# GPS_Tracker_Base_Station.net
KiCad netlist of a schematic drawn in EAGLE
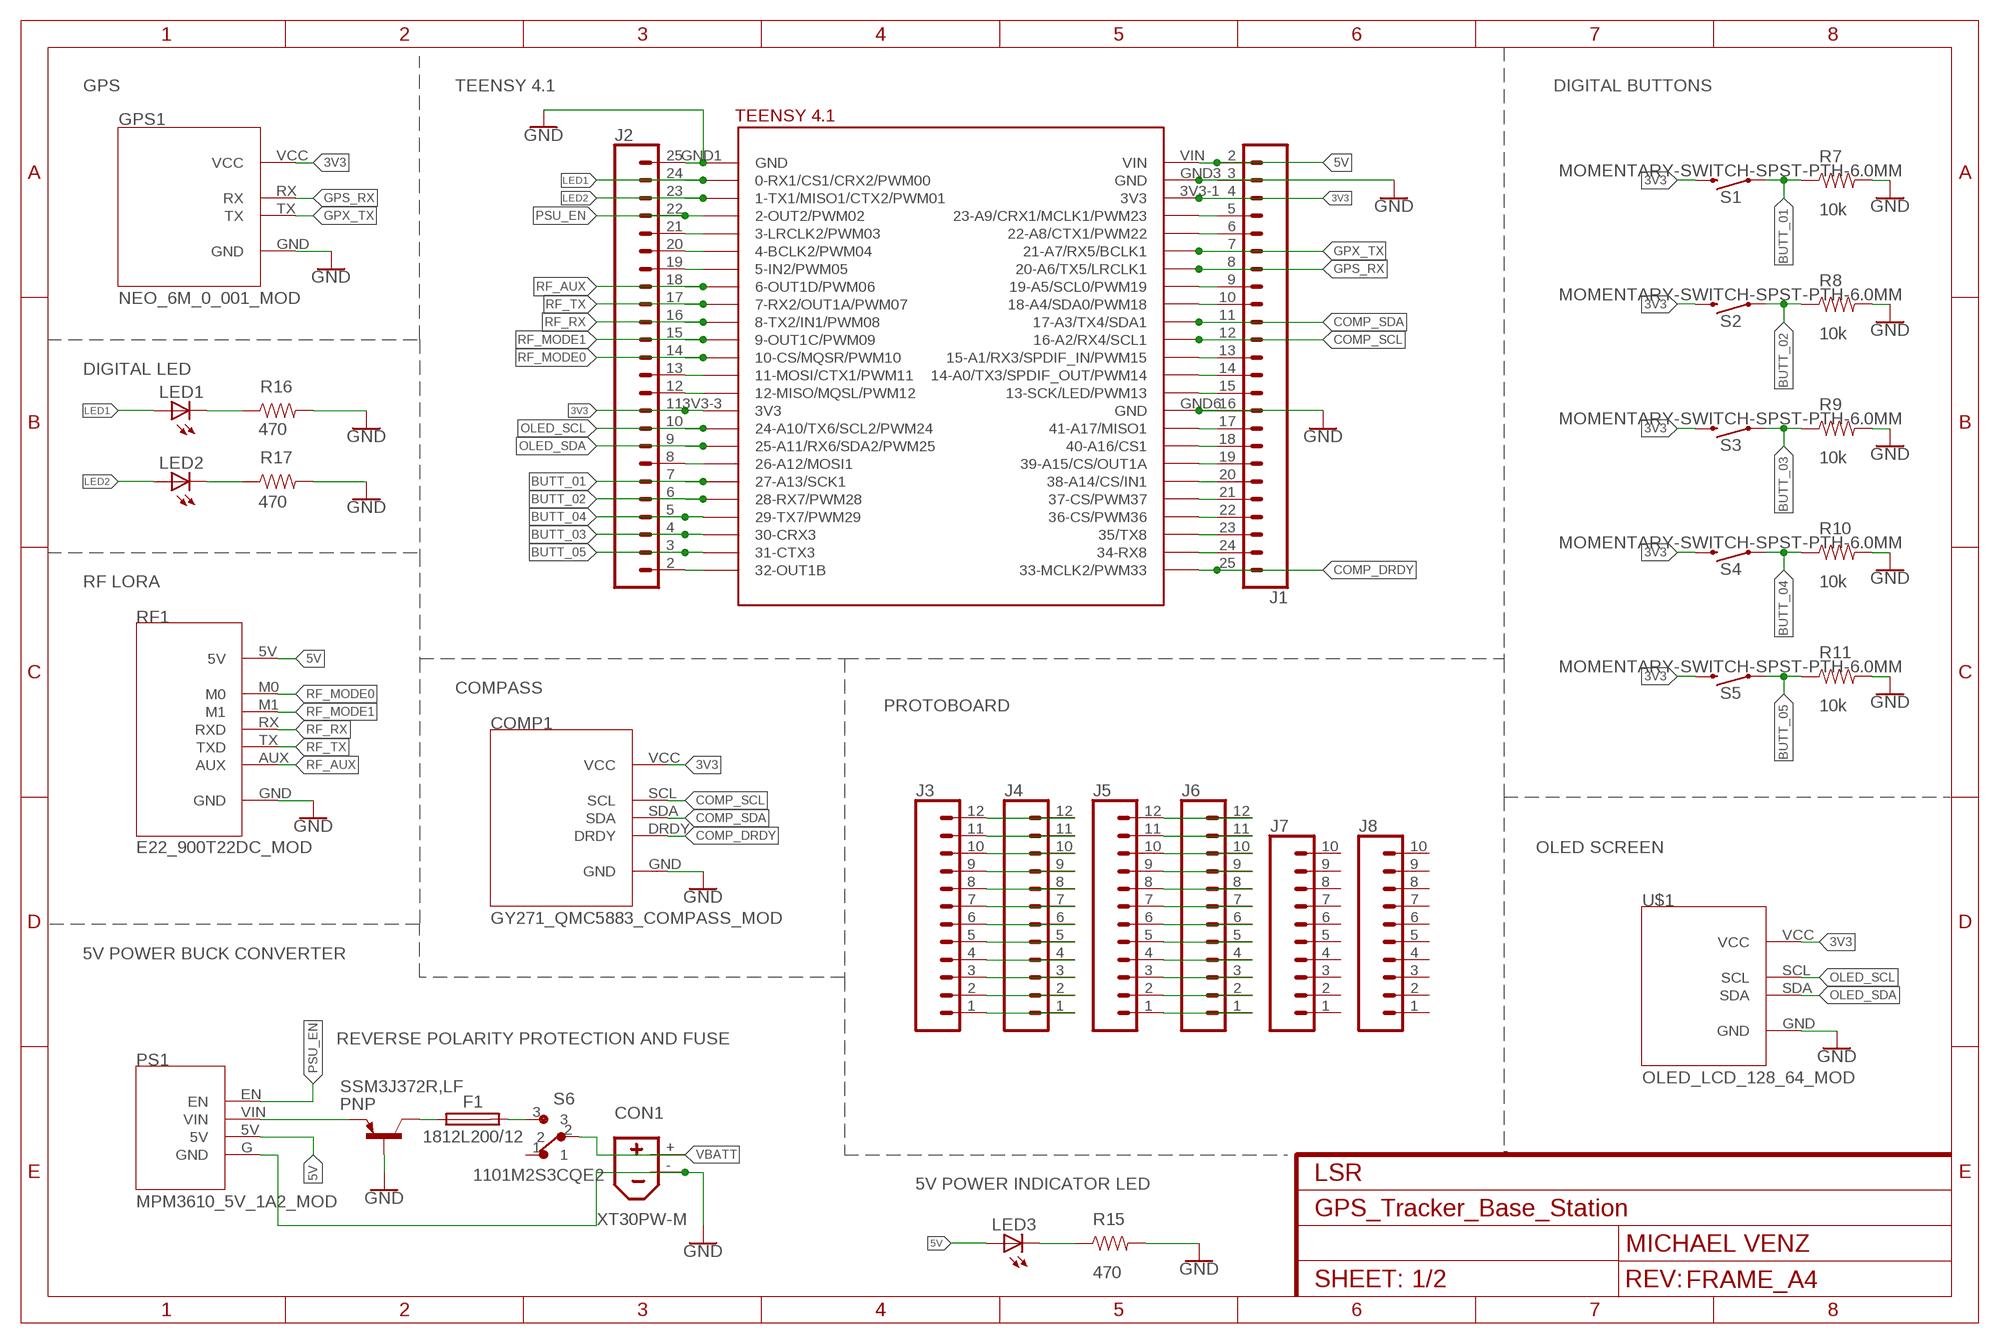
[diagram p0: schematic, sheet 1]
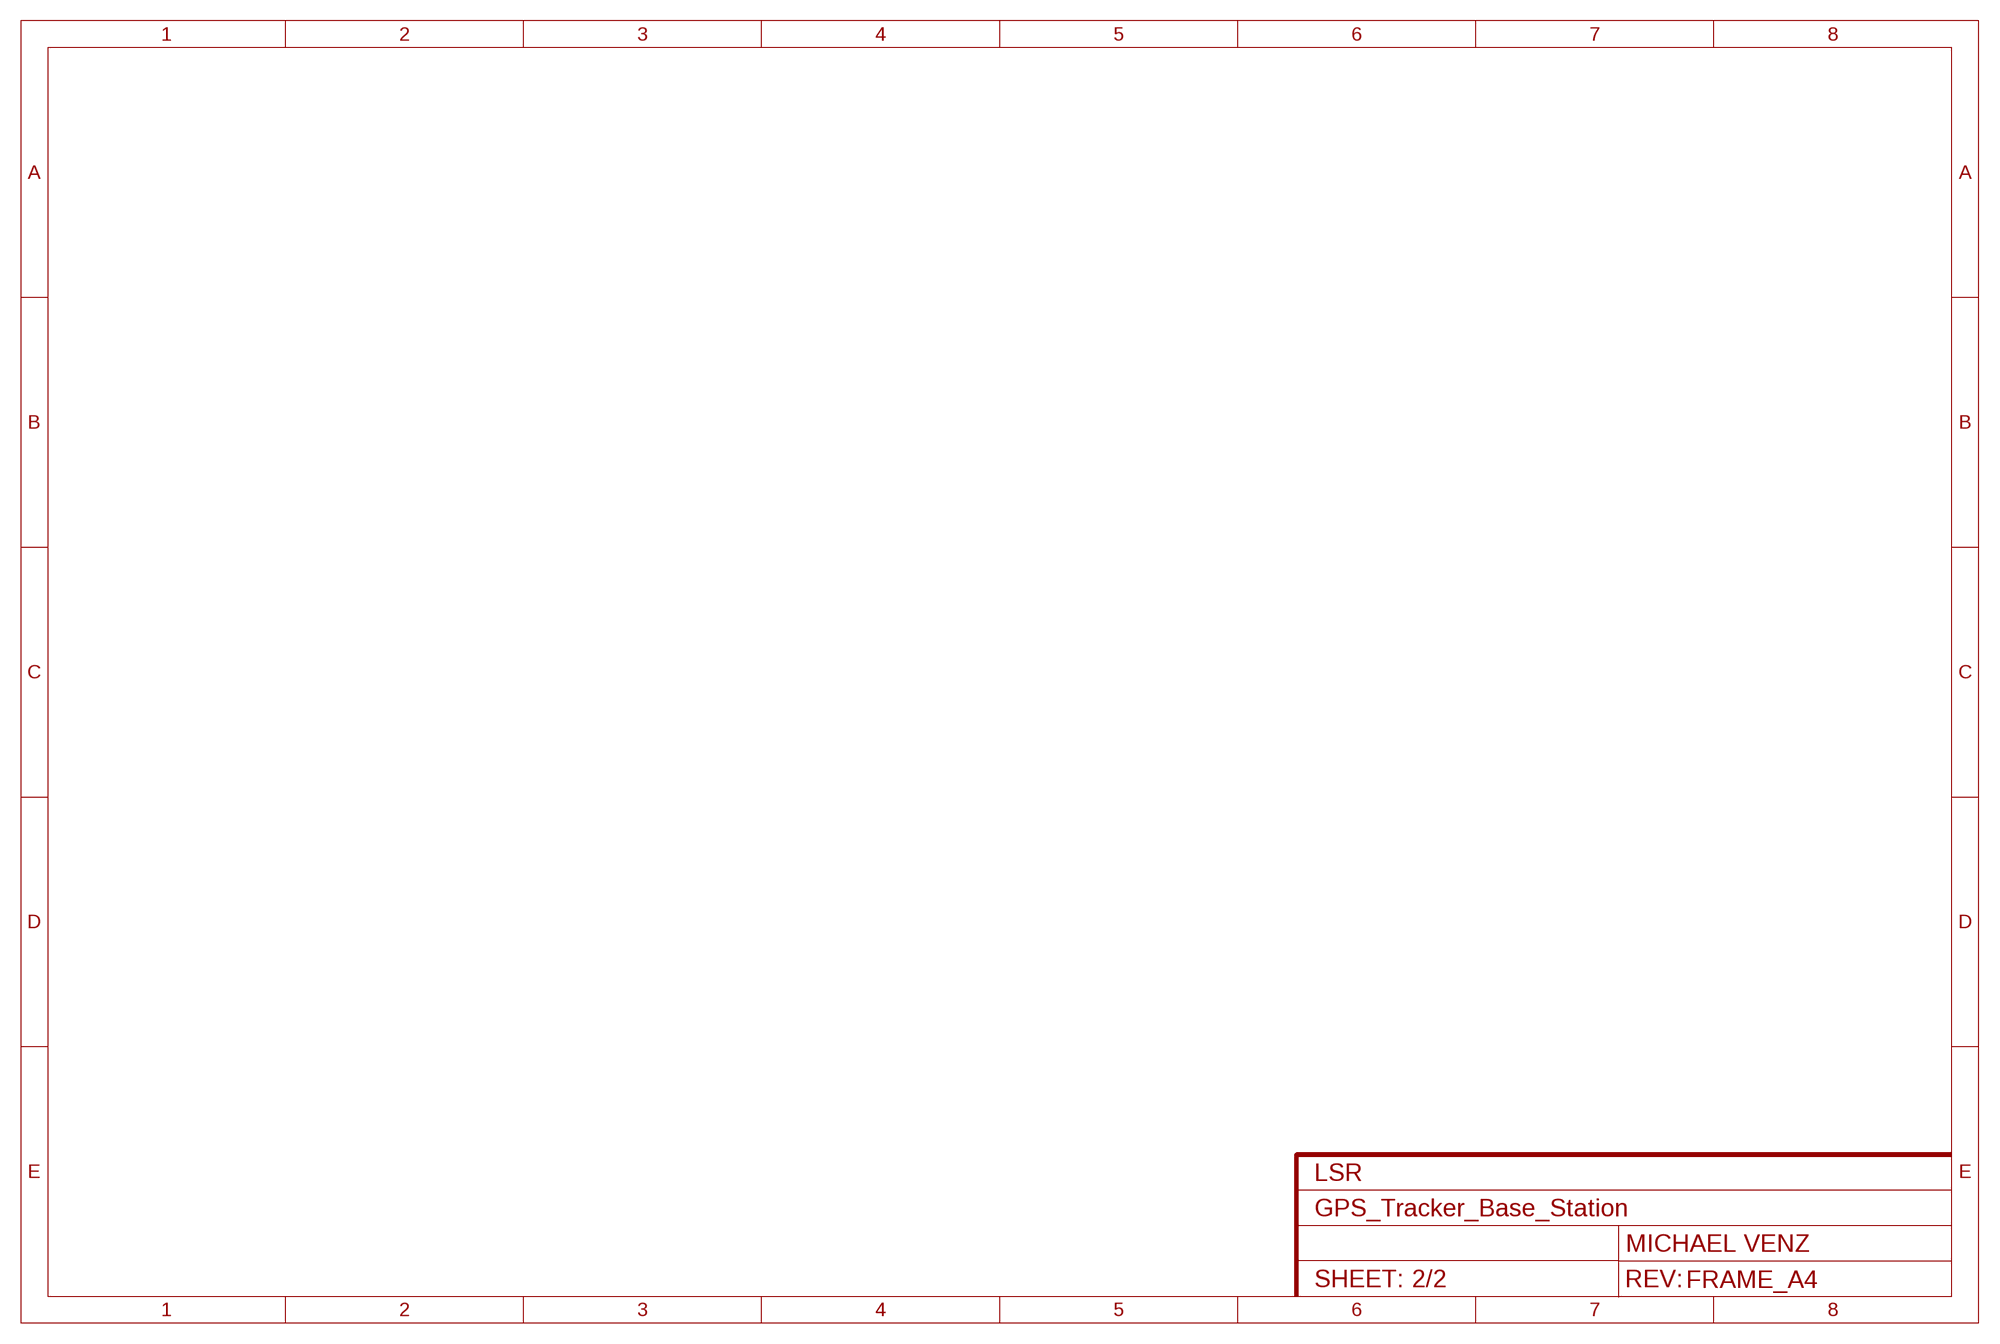
[diagram p1: schematic, sheet 2]

(export (version "E")
  (design (tool "Eeschema 10.0.6"))
  (components
    (comp (ref "COMP1")
      (value "GY271_QMC5883_COMPASS_MOD")
      (footprint "eagle-import:GY271_QMC5883_COMPASS_MOD_FP")
      (libsource (lib "eagle-import") (part "GY271_QMC5883_COMPASS_MOD"))
    )
    (comp (ref "CON1")
      (value "XT30PW-M")
      (footprint "eagle-import:XT30PW-PLUG")
      (libsource (lib "eagle-import") (part "XT30PW-M"))
    )
    (comp (ref "F1")
      (value "1812L200/12")
      (footprint "eagle-import:FUSC4532X125")
      (fields (field (name "MANUFACTURER") "Littlefuse"))
      (libsource (lib "eagle-import") (part "1812L200/12"))
    )
    (comp (ref "GPS1")
      (value "NEO_6M_0_001_MOD")
      (footprint "eagle-import:NEO_6M_0_001_MOD_FP")
      (libsource (lib "eagle-import") (part "NEO_6M_0_001_MOD"))
    )
    (comp (ref "J1")
      (value "CONN_24")
      (footprint "eagle-import:1X24")
      (libsource (lib "eagle-import") (part "CONN_24"))
    )
    (comp (ref "J2")
      (value "CONN_24")
      (footprint "eagle-import:1X24")
      (libsource (lib "eagle-import") (part "CONN_24"))
    )
    (comp (ref "J3")
      (value "CONN_12NO_SILK")
      (footprint "eagle-import:1X12_NO_SILK")
      (libsource (lib "eagle-import") (part "CONN_12NO_SILK"))
    )
    (comp (ref "J4")
      (value "CONN_12NO_SILK")
      (footprint "eagle-import:1X12_NO_SILK")
      (libsource (lib "eagle-import") (part "CONN_12NO_SILK"))
    )
    (comp (ref "J5")
      (value "CONN_12NO_SILK")
      (footprint "eagle-import:1X12_NO_SILK")
      (libsource (lib "eagle-import") (part "CONN_12NO_SILK"))
    )
    (comp (ref "J6")
      (value "CONN_12NO_SILK")
      (footprint "eagle-import:1X12_NO_SILK")
      (libsource (lib "eagle-import") (part "CONN_12NO_SILK"))
    )
    (comp (ref "J7")
      (value "CONN_10NO_SILK_PTH_FEMALE")
      (footprint "eagle-import:1X10_NO_SILK")
      (libsource (lib "eagle-import") (part "CONN_10NO_SILK_PTH_FEMALE"))
    )
    (comp (ref "J8")
      (value "CONN_10NO_SILK_PTH_FEMALE")
      (footprint "eagle-import:1X10_NO_SILK")
      (libsource (lib "eagle-import") (part "CONN_10NO_SILK_PTH_FEMALE"))
    )
    (comp (ref "LED1")
      (value "LEDCHIPLED_0805")
      (footprint "eagle-import:CHIPLED_0805")
      (libsource (lib "eagle-import") (part "LEDCHIPLED_0805"))
    )
    (comp (ref "LED2")
      (value "LEDCHIPLED_0805")
      (footprint "eagle-import:CHIPLED_0805")
      (libsource (lib "eagle-import") (part "LEDCHIPLED_0805"))
    )
    (comp (ref "LED3")
      (value "LEDCHIPLED_0805")
      (footprint "eagle-import:CHIPLED_0805")
      (libsource (lib "eagle-import") (part "LEDCHIPLED_0805"))
    )
    (comp (ref "PS1")
      (value "MPM3610_5V_1A2_MOD")
      (footprint "eagle-import:MPM3610_5V_1A2_FP")
      (libsource (lib "eagle-import") (part "MPM3610_5V_1A2_MOD"))
    )
    (comp (ref "R7")
      (value "10k")
      (footprint "eagle-import:0805_RESISTOR_FP")
      (libsource (lib "eagle-import") (part "0805_RESISTOR"))
    )
    (comp (ref "R8")
      (value "10k")
      (footprint "eagle-import:0805_RESISTOR_FP")
      (libsource (lib "eagle-import") (part "0805_RESISTOR"))
    )
    (comp (ref "R9")
      (value "10k")
      (footprint "eagle-import:0805_RESISTOR_FP")
      (libsource (lib "eagle-import") (part "0805_RESISTOR"))
    )
    (comp (ref "R10")
      (value "10k")
      (footprint "eagle-import:0805_RESISTOR_FP")
      (libsource (lib "eagle-import") (part "0805_RESISTOR"))
    )
    (comp (ref "R11")
      (value "10k")
      (footprint "eagle-import:0805_RESISTOR_FP")
      (libsource (lib "eagle-import") (part "0805_RESISTOR"))
    )
    (comp (ref "R15")
      (value "470")
      (footprint "eagle-import:0805_RESISTOR_FP")
      (libsource (lib "eagle-import") (part "0805_RESISTOR"))
    )
    (comp (ref "R16")
      (value "470")
      (footprint "eagle-import:0805_RESISTOR_FP")
      (libsource (lib "eagle-import") (part "0805_RESISTOR"))
    )
    (comp (ref "R17")
      (value "470")
      (footprint "eagle-import:0805_RESISTOR_FP")
      (libsource (lib "eagle-import") (part "0805_RESISTOR"))
    )
    (comp (ref "RF1")
      (value "E22_900T22DC_MOD")
      (footprint "eagle-import:E22_900T22DC_MOD_FP")
      (libsource (lib "eagle-import") (part "E22_900T22DC_MOD"))
    )
    (comp (ref "S1")
      (value "MOMENTARY-SWITCH-SPST-PTH-6.0MM")
      (footprint "eagle-import:TACTILE_SWITCH_PTH_6.0MM")
      (libsource (lib "eagle-import") (part "MOMENTARY-SWITCH-SPST-PTH-6.0MM"))
    )
    (comp (ref "S2")
      (value "MOMENTARY-SWITCH-SPST-PTH-6.0MM")
      (footprint "eagle-import:TACTILE_SWITCH_PTH_6.0MM")
      (libsource (lib "eagle-import") (part "MOMENTARY-SWITCH-SPST-PTH-6.0MM"))
    )
    (comp (ref "S3")
      (value "MOMENTARY-SWITCH-SPST-PTH-6.0MM")
      (footprint "eagle-import:TACTILE_SWITCH_PTH_6.0MM")
      (libsource (lib "eagle-import") (part "MOMENTARY-SWITCH-SPST-PTH-6.0MM"))
    )
    (comp (ref "S4")
      (value "MOMENTARY-SWITCH-SPST-PTH-6.0MM")
      (footprint "eagle-import:TACTILE_SWITCH_PTH_6.0MM")
      (libsource (lib "eagle-import") (part "MOMENTARY-SWITCH-SPST-PTH-6.0MM"))
    )
    (comp (ref "S5")
      (value "MOMENTARY-SWITCH-SPST-PTH-6.0MM")
      (footprint "eagle-import:TACTILE_SWITCH_PTH_6.0MM")
      (libsource (lib "eagle-import") (part "MOMENTARY-SWITCH-SPST-PTH-6.0MM"))
    )
    (comp (ref "S6")
      (value "1101M2S3CQE2")
      (footprint "eagle-import:SW_1101M2S3CQE2")
      (fields (field (name "DIGI-KEY_PART_NUMBER") "CKN5001-ND") (field (name "MF") "C&K"))
      (libsource (lib "eagle-import") (part "1101M2S3CQE2"))
    )
    (comp (ref "SSM3J372R,LF")
      (value "PNP")
      (footprint "eagle-import:SOT95P237X112-3N")
      (libsource (lib "eagle-import") (part "PNPSOT23_"))
    )
    (comp (ref "U$1")
      (value "OLED_LCD_128_64_MOD")
      (footprint "eagle-import:OLED_LCD_128_64_MOD_FP")
      (libsource (lib "eagle-import") (part "OLED_LCD_128_64_MOD"))
    )
    (comp (ref "U$3")
      (value "TEENSY_4_1")
      (footprint "eagle-import:TEENSY_4_1_FP")
      (libsource (lib "eagle-import") (part "TEENSY_4_1"))
    )
  )
  (nets
    (net (code "1") (name "3V3") (class "Default")
      (node (ref "COMP1") (pin "VCC") (pinfunction "VCC_VCC") (pintype "bidirectional"))
      (node (ref "GPS1") (pin "VCC") (pinfunction "VCC_VCC") (pintype "bidirectional"))
      (node (ref "J1") (pin "4") (pinfunction "4_4") (pintype "passive"))
      (node (ref "J2") (pin "11") (pinfunction "11_11") (pintype "passive"))
      (node (ref "S1") (pin "3") (pinfunction "2_3") (pintype "passive"))
      (node (ref "S2") (pin "3") (pinfunction "2_3") (pintype "passive"))
      (node (ref "S3") (pin "3") (pinfunction "2_3") (pintype "passive"))
      (node (ref "S4") (pin "3") (pinfunction "2_3") (pintype "passive"))
      (node (ref "S5") (pin "3") (pinfunction "2_3") (pintype "passive"))
      (node (ref "U$1") (pin "VCC") (pinfunction "VCC_VCC") (pintype "bidirectional"))
      (node (ref "U$3") (pin "3V3-1") (pinfunction "3V3_3V3-1") (pintype "bidirectional"))
      (node (ref "U$3") (pin "3V3-3") (pinfunction "3V3_3V3-3") (pintype "bidirectional"))
    )
    (net (code "2") (name "5V") (class "Default")
      (node (ref "J1") (pin "2") (pinfunction "2_2") (pintype "passive"))
      (node (ref "LED3") (pin "A") (pinfunction "A_A") (pintype "passive"))
      (node (ref "PS1") (pin "5V") (pinfunction "5V_5V") (pintype "bidirectional"))
      (node (ref "RF1") (pin "5V") (pinfunction "5V_5V") (pintype "bidirectional"))
      (node (ref "U$3") (pin "VIN") (pinfunction "VIN_VIN") (pintype "bidirectional"))
    )
    (net (code "3") (name "BUTT_01") (class "Default")
      (node (ref "J2") (pin "7") (pinfunction "7_7") (pintype "passive"))
      (node (ref "R7") (pin "1") (pinfunction "1_1") (pintype "passive"))
      (node (ref "S1") (pin "1") (pinfunction "1_1") (pintype "passive"))
      (node (ref "U$3") (pin "27-A13/SCK1") (pinfunction "27-A13/SCK1_27-A13/SCK1") (pintype "bidirectional"))
    )
    (net (code "4") (name "BUTT_02") (class "Default")
      (node (ref "J2") (pin "6") (pinfunction "6_6") (pintype "passive"))
      (node (ref "R8") (pin "1") (pinfunction "1_1") (pintype "passive"))
      (node (ref "S2") (pin "1") (pinfunction "1_1") (pintype "passive"))
      (node (ref "U$3") (pin "28-RX7/PWM28") (pinfunction "28-RX7/PWM28_28-RX7/PWM28") (pintype "bidirectional"))
    )
    (net (code "5") (name "BUTT_03") (class "Default")
      (node (ref "J2") (pin "4") (pinfunction "4_4") (pintype "passive"))
      (node (ref "R9") (pin "1") (pinfunction "1_1") (pintype "passive"))
      (node (ref "S3") (pin "1") (pinfunction "1_1") (pintype "passive"))
      (node (ref "U$3") (pin "30-CRX3") (pinfunction "30-CRX3_30-CRX3") (pintype "bidirectional"))
    )
    (net (code "6") (name "BUTT_04") (class "Default")
      (node (ref "J2") (pin "5") (pinfunction "5_5") (pintype "passive"))
      (node (ref "R10") (pin "1") (pinfunction "1_1") (pintype "passive"))
      (node (ref "S4") (pin "1") (pinfunction "1_1") (pintype "passive"))
      (node (ref "U$3") (pin "29-TX7/PWM29") (pinfunction "29-TX7/PWM29_29-TX7/PWM29") (pintype "bidirectional"))
    )
    (net (code "7") (name "BUTT_05") (class "Default")
      (node (ref "J2") (pin "3") (pinfunction "3_3") (pintype "passive"))
      (node (ref "R11") (pin "1") (pinfunction "1_1") (pintype "passive"))
      (node (ref "S5") (pin "1") (pinfunction "1_1") (pintype "passive"))
      (node (ref "U$3") (pin "31-CTX3") (pinfunction "31-CTX3_31-CTX3") (pintype "bidirectional"))
    )
    (net (code "8") (name "COMP_DRDY") (class "Default")
      (node (ref "COMP1") (pin "DRDY") (pinfunction "DRDY_DRDY") (pintype "bidirectional"))
      (node (ref "J1") (pin "25") (pinfunction "25_25") (pintype "passive"))
      (node (ref "U$3") (pin "33-MCLK2/PWM33") (pinfunction "33-MCLK2/PWM33_33-MCLK2/PWM33") (pintype "bidirectional"))
    )
    (net (code "9") (name "COMP_SCL") (class "Default")
      (node (ref "COMP1") (pin "SCL") (pinfunction "SCL_SCL") (pintype "bidirectional"))
      (node (ref "J1") (pin "12") (pinfunction "12_12") (pintype "passive"))
      (node (ref "U$3") (pin "16-A2/RX4/SCL1") (pinfunction "16-A2/RX4/SCL1_16-A2/RX4/SCL1") (pintype "bidirectional"))
    )
    (net (code "10") (name "COMP_SDA") (class "Default")
      (node (ref "COMP1") (pin "SDA") (pinfunction "SDA_SDA") (pintype "bidirectional"))
      (node (ref "J1") (pin "11") (pinfunction "11_11") (pintype "passive"))
      (node (ref "U$3") (pin "17-A3/TX4/SDA1") (pinfunction "17-A3/TX4/SDA1_17-A3/TX4/SDA1") (pintype "bidirectional"))
    )
    (net (code "11") (name "GND") (class "Default")
      (node (ref "COMP1") (pin "GND") (pinfunction "GND_GND") (pintype "bidirectional"))
      (node (ref "CON1") (pin "-") (pinfunction "-_-") (pintype "power_in"))
      (node (ref "GPS1") (pin "GND") (pinfunction "GND_GND") (pintype "bidirectional"))
      (node (ref "J1") (pin "16") (pinfunction "16_16") (pintype "passive"))
      (node (ref "J1") (pin "3") (pinfunction "3_3") (pintype "passive"))
      (node (ref "J2") (pin "25") (pinfunction "25_25") (pintype "passive"))
      (node (ref "PS1") (pin "G") (pinfunction "GND_G") (pintype "bidirectional"))
      (node (ref "R10") (pin "2") (pinfunction "2_2") (pintype "passive"))
      (node (ref "R11") (pin "2") (pinfunction "2_2") (pintype "passive"))
      (node (ref "R15") (pin "2") (pinfunction "2_2") (pintype "passive"))
      (node (ref "R16") (pin "2") (pinfunction "2_2") (pintype "passive"))
      (node (ref "R17") (pin "2") (pinfunction "2_2") (pintype "passive"))
      (node (ref "R7") (pin "2") (pinfunction "2_2") (pintype "passive"))
      (node (ref "R8") (pin "2") (pinfunction "2_2") (pintype "passive"))
      (node (ref "R9") (pin "2") (pinfunction "2_2") (pintype "passive"))
      (node (ref "RF1") (pin "GND") (pinfunction "GND_GND") (pintype "bidirectional"))
      (node (ref "SSM3J372R,LF") (pin "1") (pinfunction "B_1") (pintype "passive"))
      (node (ref "U$1") (pin "GND") (pinfunction "GND_GND") (pintype "bidirectional"))
      (node (ref "U$3") (pin "GND1") (pinfunction "GND_GND1") (pintype "bidirectional"))
      (node (ref "U$3") (pin "GND3") (pinfunction "GND_GND3") (pintype "bidirectional"))
      (node (ref "U$3") (pin "GND6") (pinfunction "GND_GND6") (pintype "bidirectional"))
    )
    (net (code "12") (name "GPS_RX") (class "Default")
      (node (ref "GPS1") (pin "RX") (pinfunction "RX_RX") (pintype "bidirectional"))
      (node (ref "J1") (pin "8") (pinfunction "8_8") (pintype "passive"))
      (node (ref "U$3") (pin "20-A6/TX5/LRCLK1") (pinfunction "20-A6/TX5/LRCLK1_20-A6/TX5/LRCLK1") (pintype "bidirectional"))
    )
    (net (code "13") (name "GPX_TX") (class "Default")
      (node (ref "GPS1") (pin "TX") (pinfunction "TX_TX") (pintype "bidirectional"))
      (node (ref "J1") (pin "7") (pinfunction "7_7") (pintype "passive"))
      (node (ref "U$3") (pin "21-A7/RX5/BCLK1") (pinfunction "21-A7/RX5/BCLK1_21-A7/RX5/BCLK1") (pintype "bidirectional"))
    )
    (net (code "14") (name "LED1") (class "Default")
      (node (ref "J2") (pin "24") (pinfunction "24_24") (pintype "passive"))
      (node (ref "LED1") (pin "A") (pinfunction "A_A") (pintype "passive"))
      (node (ref "U$3") (pin "0-RX1/CS1/CRX2/PWM00") (pinfunction "0-RX1/CS1/CRX2/PWM00_0-RX1/CS1/CRX2/PWM00") (pintype "bidirectional"))
    )
    (net (code "15") (name "LED2") (class "Default")
      (node (ref "J2") (pin "23") (pinfunction "23_23") (pintype "passive"))
      (node (ref "LED2") (pin "A") (pinfunction "A_A") (pintype "passive"))
      (node (ref "U$3") (pin "1-TX1/MISO1/CTX2/PWM01") (pinfunction "1-TX1/MISO1/CTX2/PWM01_1-TX1/MISO1/CTX2/PWM01") (pintype "bidirectional"))
    )
    (net (code "16") (name "Net-(F1-Pad2)") (class "Default")
      (node (ref "F1") (pin "2") (pinfunction "2_2") (pintype "passive"))
      (node (ref "S6") (pin "3") (pinfunction "3_3") (pintype "passive"))
    )
    (net (code "17") (name "Net-(J1-Pad5)") (class "Default")
      (node (ref "J1") (pin "5") (pinfunction "5_5") (pintype "passive"))
      (node (ref "U$3") (pin "23-A9/CRX1/MCLK1/PWM23") (pinfunction "23-A9/CRX1/MCLK1/PWM23_23-A9/CRX1/MCLK1/PWM23") (pintype "bidirectional"))
    )
    (net (code "18") (name "Net-(J1-Pad6)") (class "Default")
      (node (ref "J1") (pin "6") (pinfunction "6_6") (pintype "passive"))
      (node (ref "U$3") (pin "22-A8/CTX1/PWM22") (pinfunction "22-A8/CTX1/PWM22_22-A8/CTX1/PWM22") (pintype "bidirectional"))
    )
    (net (code "19") (name "Net-(J1-Pad9)") (class "Default")
      (node (ref "J1") (pin "9") (pinfunction "9_9") (pintype "passive"))
      (node (ref "U$3") (pin "19-A5/SCL0/PWM19") (pinfunction "19-A5/SCL0/PWM19_19-A5/SCL0/PWM19") (pintype "bidirectional"))
    )
    (net (code "20") (name "Net-(J1-Pad10)") (class "Default")
      (node (ref "J1") (pin "10") (pinfunction "10_10") (pintype "passive"))
      (node (ref "U$3") (pin "18-A4/SDA0/PWM18") (pinfunction "18-A4/SDA0/PWM18_18-A4/SDA0/PWM18") (pintype "bidirectional"))
    )
    (net (code "21") (name "Net-(J1-Pad13)") (class "Default")
      (node (ref "J1") (pin "13") (pinfunction "13_13") (pintype "passive"))
      (node (ref "U$3") (pin "15-A1/RX3/SPDIF_IN/PWM15") (pinfunction "15-A1/RX3/SPDIF_IN/PWM15_15-A1/RX3/SPDIF_IN/PWM15") (pintype "bidirectional"))
    )
    (net (code "22") (name "Net-(J1-Pad14)") (class "Default")
      (node (ref "J1") (pin "14") (pinfunction "14_14") (pintype "passive"))
      (node (ref "U$3") (pin "14-A0/TX3/SPDIF_OUT/PWM14") (pinfunction "14-A0/TX3/SPDIF_OUT/PWM14_14-A0/TX3/SPDIF_OUT/PWM14") (pintype "bidirectional"))
    )
    (net (code "23") (name "Net-(J1-Pad15)") (class "Default")
      (node (ref "J1") (pin "15") (pinfunction "15_15") (pintype "passive"))
      (node (ref "U$3") (pin "13-SCK/LED/PWM13") (pinfunction "13-SCK/LED/PWM13_13-SCK/LED/PWM13") (pintype "bidirectional"))
    )
    (net (code "24") (name "Net-(J1-Pad17)") (class "Default")
      (node (ref "J1") (pin "17") (pinfunction "17_17") (pintype "passive"))
      (node (ref "U$3") (pin "41-A17/MISO1") (pinfunction "41-A17/MISO1_41-A17/MISO1") (pintype "bidirectional"))
    )
    (net (code "25") (name "Net-(J1-Pad18)") (class "Default")
      (node (ref "J1") (pin "18") (pinfunction "18_18") (pintype "passive"))
      (node (ref "U$3") (pin "40-A16/CS1") (pinfunction "40-A16/CS1_40-A16/CS1") (pintype "bidirectional"))
    )
    (net (code "26") (name "Net-(J1-Pad19)") (class "Default")
      (node (ref "J1") (pin "19") (pinfunction "19_19") (pintype "passive"))
      (node (ref "U$3") (pin "39-A15/CS/OUT1A") (pinfunction "39-A15/CS/OUT1A_39-A15/CS/OUT1A") (pintype "bidirectional"))
    )
    (net (code "27") (name "Net-(J1-Pad20)") (class "Default")
      (node (ref "J1") (pin "20") (pinfunction "20_20") (pintype "passive"))
      (node (ref "U$3") (pin "38-A14/CS/IN1") (pinfunction "38-A14/CS/IN1_38-A14/CS/IN1") (pintype "bidirectional"))
    )
    (net (code "28") (name "Net-(J1-Pad21)") (class "Default")
      (node (ref "J1") (pin "21") (pinfunction "21_21") (pintype "passive"))
      (node (ref "U$3") (pin "37-CS/PWM37") (pinfunction "37-CS/PWM37_37-CS/PWM37") (pintype "bidirectional"))
    )
    (net (code "29") (name "Net-(J1-Pad22)") (class "Default")
      (node (ref "J1") (pin "22") (pinfunction "22_22") (pintype "passive"))
      (node (ref "U$3") (pin "36-CS/PWM36") (pinfunction "36-CS/PWM36_36-CS/PWM36") (pintype "bidirectional"))
    )
    (net (code "30") (name "Net-(J1-Pad24)") (class "Default")
      (node (ref "J1") (pin "24") (pinfunction "24_24") (pintype "passive"))
      (node (ref "U$3") (pin "34-RX8") (pinfunction "34-RX8_34-RX8") (pintype "bidirectional"))
    )
    (net (code "31") (name "Net-(J2-Pad2)") (class "Default")
      (node (ref "J2") (pin "2") (pinfunction "2_2") (pintype "passive"))
      (node (ref "U$3") (pin "32-OUT1B") (pinfunction "32-OUT1B_32-OUT1B") (pintype "bidirectional"))
    )
    (net (code "32") (name "Net-(J2-Pad8)") (class "Default")
      (node (ref "J2") (pin "8") (pinfunction "8_8") (pintype "passive"))
      (node (ref "U$3") (pin "26-A12/MOSI1") (pinfunction "26-A12/MOSI1_26-A12/MOSI1") (pintype "bidirectional"))
    )
    (net (code "33") (name "Net-(J2-Pad12)") (class "Default")
      (node (ref "J2") (pin "12") (pinfunction "12_12") (pintype "passive"))
      (node (ref "U$3") (pin "12-MISO/MQSL/PWM12") (pinfunction "12-MISO/MQSL/PWM12_12-MISO/MQSL/PWM12") (pintype "bidirectional"))
    )
    (net (code "34") (name "Net-(J2-Pad13)") (class "Default")
      (node (ref "J2") (pin "13") (pinfunction "13_13") (pintype "passive"))
      (node (ref "U$3") (pin "11-MOSI/CTX1/PWM11") (pinfunction "11-MOSI/CTX1/PWM11_11-MOSI/CTX1/PWM11") (pintype "bidirectional"))
    )
    (net (code "35") (name "Net-(J2-Pad19)") (class "Default")
      (node (ref "J2") (pin "19") (pinfunction "19_19") (pintype "passive"))
      (node (ref "U$3") (pin "5-IN2/PWM05") (pinfunction "5-IN2/PWM05_5-IN2/PWM05") (pintype "bidirectional"))
    )
    (net (code "36") (name "Net-(J2-Pad20)") (class "Default")
      (node (ref "J2") (pin "20") (pinfunction "20_20") (pintype "passive"))
      (node (ref "U$3") (pin "4-BCLK2/PWM04") (pinfunction "4-BCLK2/PWM04_4-BCLK2/PWM04") (pintype "bidirectional"))
    )
    (net (code "37") (name "Net-(J2-Pad21)") (class "Default")
      (node (ref "J2") (pin "21") (pinfunction "21_21") (pintype "passive"))
      (node (ref "U$3") (pin "3-LRCLK2/PWM03") (pinfunction "3-LRCLK2/PWM03_3-LRCLK2/PWM03") (pintype "bidirectional"))
    )
    (net (code "38") (name "Net-(J3-Pad1)") (class "Default")
      (node (ref "J3") (pin "1") (pinfunction "1_1") (pintype "passive"))
      (node (ref "J4") (pin "1") (pinfunction "1_1") (pintype "passive"))
    )
    (net (code "39") (name "Net-(J3-Pad2)") (class "Default")
      (node (ref "J3") (pin "2") (pinfunction "2_2") (pintype "passive"))
      (node (ref "J4") (pin "2") (pinfunction "2_2") (pintype "passive"))
    )
    (net (code "40") (name "Net-(J3-Pad3)") (class "Default")
      (node (ref "J3") (pin "3") (pinfunction "3_3") (pintype "passive"))
      (node (ref "J4") (pin "3") (pinfunction "3_3") (pintype "passive"))
    )
    (net (code "41") (name "Net-(J3-Pad4)") (class "Default")
      (node (ref "J3") (pin "4") (pinfunction "4_4") (pintype "passive"))
      (node (ref "J4") (pin "4") (pinfunction "4_4") (pintype "passive"))
    )
    (net (code "42") (name "Net-(J3-Pad5)") (class "Default")
      (node (ref "J3") (pin "5") (pinfunction "5_5") (pintype "passive"))
      (node (ref "J4") (pin "5") (pinfunction "5_5") (pintype "passive"))
    )
    (net (code "43") (name "Net-(J3-Pad6)") (class "Default")
      (node (ref "J3") (pin "6") (pinfunction "6_6") (pintype "passive"))
      (node (ref "J4") (pin "6") (pinfunction "6_6") (pintype "passive"))
    )
    (net (code "44") (name "Net-(J3-Pad7)") (class "Default")
      (node (ref "J3") (pin "7") (pinfunction "7_7") (pintype "passive"))
      (node (ref "J4") (pin "7") (pinfunction "7_7") (pintype "passive"))
    )
    (net (code "45") (name "Net-(J3-Pad8)") (class "Default")
      (node (ref "J3") (pin "8") (pinfunction "8_8") (pintype "passive"))
      (node (ref "J4") (pin "8") (pinfunction "8_8") (pintype "passive"))
    )
    (net (code "46") (name "Net-(J3-Pad9)") (class "Default")
      (node (ref "J3") (pin "9") (pinfunction "9_9") (pintype "passive"))
      (node (ref "J4") (pin "9") (pinfunction "9_9") (pintype "passive"))
    )
    (net (code "47") (name "Net-(J3-Pad10)") (class "Default")
      (node (ref "J3") (pin "10") (pinfunction "10_10") (pintype "passive"))
      (node (ref "J4") (pin "10") (pinfunction "10_10") (pintype "passive"))
    )
    (net (code "48") (name "Net-(J3-Pad11)") (class "Default")
      (node (ref "J3") (pin "11") (pinfunction "11_11") (pintype "passive"))
      (node (ref "J4") (pin "11") (pinfunction "11_11") (pintype "passive"))
    )
    (net (code "49") (name "Net-(J3-Pad12)") (class "Default")
      (node (ref "J3") (pin "12") (pinfunction "12_12") (pintype "passive"))
      (node (ref "J4") (pin "12") (pinfunction "12_12") (pintype "passive"))
    )
    (net (code "50") (name "Net-(J5-Pad1)") (class "Default")
      (node (ref "J5") (pin "1") (pinfunction "1_1") (pintype "passive"))
      (node (ref "J6") (pin "1") (pinfunction "1_1") (pintype "passive"))
    )
    (net (code "51") (name "Net-(J5-Pad2)") (class "Default")
      (node (ref "J5") (pin "2") (pinfunction "2_2") (pintype "passive"))
      (node (ref "J6") (pin "2") (pinfunction "2_2") (pintype "passive"))
    )
    (net (code "52") (name "Net-(J5-Pad3)") (class "Default")
      (node (ref "J5") (pin "3") (pinfunction "3_3") (pintype "passive"))
      (node (ref "J6") (pin "3") (pinfunction "3_3") (pintype "passive"))
    )
    (net (code "53") (name "Net-(J5-Pad4)") (class "Default")
      (node (ref "J5") (pin "4") (pinfunction "4_4") (pintype "passive"))
      (node (ref "J6") (pin "4") (pinfunction "4_4") (pintype "passive"))
    )
    (net (code "54") (name "Net-(J5-Pad5)") (class "Default")
      (node (ref "J5") (pin "5") (pinfunction "5_5") (pintype "passive"))
      (node (ref "J6") (pin "5") (pinfunction "5_5") (pintype "passive"))
    )
    (net (code "55") (name "Net-(J5-Pad6)") (class "Default")
      (node (ref "J5") (pin "6") (pinfunction "6_6") (pintype "passive"))
      (node (ref "J6") (pin "6") (pinfunction "6_6") (pintype "passive"))
    )
    (net (code "56") (name "Net-(J5-Pad7)") (class "Default")
      (node (ref "J5") (pin "7") (pinfunction "7_7") (pintype "passive"))
      (node (ref "J6") (pin "7") (pinfunction "7_7") (pintype "passive"))
    )
    (net (code "57") (name "Net-(J5-Pad8)") (class "Default")
      (node (ref "J5") (pin "8") (pinfunction "8_8") (pintype "passive"))
      (node (ref "J6") (pin "8") (pinfunction "8_8") (pintype "passive"))
    )
    (net (code "58") (name "Net-(J5-Pad9)") (class "Default")
      (node (ref "J5") (pin "9") (pinfunction "9_9") (pintype "passive"))
      (node (ref "J6") (pin "9") (pinfunction "9_9") (pintype "passive"))
    )
    (net (code "59") (name "Net-(J5-Pad10)") (class "Default")
      (node (ref "J5") (pin "10") (pinfunction "10_10") (pintype "passive"))
      (node (ref "J6") (pin "10") (pinfunction "10_10") (pintype "passive"))
    )
    (net (code "60") (name "Net-(J5-Pad11)") (class "Default")
      (node (ref "J5") (pin "11") (pinfunction "11_11") (pintype "passive"))
      (node (ref "J6") (pin "11") (pinfunction "11_11") (pintype "passive"))
    )
    (net (code "61") (name "Net-(J5-Pad12)") (class "Default")
      (node (ref "J5") (pin "12") (pinfunction "12_12") (pintype "passive"))
      (node (ref "J6") (pin "12") (pinfunction "12_12") (pintype "passive"))
    )
    (net (code "62") (name "Net-(LED1-PadC)") (class "Default")
      (node (ref "LED1") (pin "C") (pinfunction "C_C") (pintype "passive"))
      (node (ref "R16") (pin "1") (pinfunction "1_1") (pintype "passive"))
    )
    (net (code "63") (name "Net-(LED2-PadC)") (class "Default")
      (node (ref "LED2") (pin "C") (pinfunction "C_C") (pintype "passive"))
      (node (ref "R17") (pin "1") (pinfunction "1_1") (pintype "passive"))
    )
    (net (code "64") (name "Net-(LED3-PadC)") (class "Default")
      (node (ref "LED3") (pin "C") (pinfunction "C_C") (pintype "passive"))
      (node (ref "R15") (pin "1") (pinfunction "1_1") (pintype "passive"))
    )
    (net (code "65") (name "Net-(SSM3J372R,LF-C)") (class "Default")
      (node (ref "F1") (pin "1") (pinfunction "1_1") (pintype "passive"))
      (node (ref "SSM3J372R,LF") (pin "3") (pinfunction "C_3") (pintype "passive"))
    )
    (net (code "66") (name "Net-(SSM3J372R,LF-E)") (class "Default")
      (node (ref "PS1") (pin "VIN") (pinfunction "VIN_VIN") (pintype "bidirectional"))
      (node (ref "SSM3J372R,LF") (pin "2") (pinfunction "E_2") (pintype "passive"))
    )
    (net (code "67") (name "Net-(U$3-35{slash}TX8)") (class "Default")
      (node (ref "J1") (pin "23") (pinfunction "23_23") (pintype "passive"))
      (node (ref "U$3") (pin "35-TX8") (pinfunction "35/TX8_35-TX8") (pintype "bidirectional"))
    )
    (net (code "68") (name "OLED_SCL") (class "Default")
      (node (ref "J2") (pin "10") (pinfunction "10_10") (pintype "passive"))
      (node (ref "U$1") (pin "SCL") (pinfunction "SCL_SCL") (pintype "bidirectional"))
      (node (ref "U$3") (pin "24-A10/TX6/SCL2/PWM24") (pinfunction "24-A10/TX6/SCL2/PWM24_24-A10/TX6/SCL2/PWM24") (pintype "bidirectional"))
    )
    (net (code "69") (name "OLED_SDA") (class "Default")
      (node (ref "J2") (pin "9") (pinfunction "9_9") (pintype "passive"))
      (node (ref "U$1") (pin "SDA") (pinfunction "SDA_SDA") (pintype "bidirectional"))
      (node (ref "U$3") (pin "25-A11/RX6/SDA2/PWM25") (pinfunction "25-A11/RX6/SDA2/PWM25_25-A11/RX6/SDA2/PWM25") (pintype "bidirectional"))
    )
    (net (code "70") (name "PSU_EN") (class "Default")
      (node (ref "J2") (pin "22") (pinfunction "22_22") (pintype "passive"))
      (node (ref "PS1") (pin "EN") (pinfunction "EN_EN") (pintype "bidirectional"))
      (node (ref "U$3") (pin "2-OUT2/PWM02") (pinfunction "2-OUT2/PWM02_2-OUT2/PWM02") (pintype "bidirectional"))
    )
    (net (code "71") (name "RF_AUX") (class "Default")
      (node (ref "J2") (pin "18") (pinfunction "18_18") (pintype "passive"))
      (node (ref "RF1") (pin "AUX") (pinfunction "AUX_AUX") (pintype "bidirectional"))
      (node (ref "U$3") (pin "6-OUT1D/PWM06") (pinfunction "6-OUT1D/PWM06_6-OUT1D/PWM06") (pintype "bidirectional"))
    )
    (net (code "72") (name "RF_MODE0") (class "Default")
      (node (ref "J2") (pin "14") (pinfunction "14_14") (pintype "passive"))
      (node (ref "RF1") (pin "M0") (pinfunction "M0_M0") (pintype "bidirectional"))
      (node (ref "U$3") (pin "10-CS\\MQSR/PWM10") (pinfunction "10-CS/MQSR/PWM10_10-CS\\MQSR/PWM10") (pintype "bidirectional"))
    )
    (net (code "73") (name "RF_MODE1") (class "Default")
      (node (ref "J2") (pin "15") (pinfunction "15_15") (pintype "passive"))
      (node (ref "RF1") (pin "M1") (pinfunction "M1_M1") (pintype "bidirectional"))
      (node (ref "U$3") (pin "9-OUT1C/PWM09") (pinfunction "9-OUT1C/PWM09_9-OUT1C/PWM09") (pintype "bidirectional"))
    )
    (net (code "74") (name "RF_RX") (class "Default")
      (node (ref "J2") (pin "16") (pinfunction "16_16") (pintype "passive"))
      (node (ref "RF1") (pin "RX") (pinfunction "RXD_RX") (pintype "bidirectional"))
      (node (ref "U$3") (pin "8-TX2/IN1/PWM08") (pinfunction "8-TX2/IN1/PWM08_8-TX2/IN1/PWM08") (pintype "bidirectional"))
    )
    (net (code "75") (name "RF_TX") (class "Default")
      (node (ref "J2") (pin "17") (pinfunction "17_17") (pintype "passive"))
      (node (ref "RF1") (pin "TX") (pinfunction "TXD_TX") (pintype "bidirectional"))
      (node (ref "U$3") (pin "7-RX2/OUT1A/PWM07") (pinfunction "7-RX2/OUT1A/PWM07_7-RX2/OUT1A/PWM07") (pintype "bidirectional"))
    )
    (net (code "76") (name "VBATT") (class "Default")
      (node (ref "CON1") (pin "+") (pinfunction "+_+") (pintype "power_in"))
      (node (ref "S6") (pin "2") (pinfunction "2_2") (pintype "passive"))
    )
    (net (code "77") (name "unconnected-(J7-Pad1)") (class "Default")
      (node (ref "J7") (pin "1") (pinfunction "1_1") (pintype "passive"))
    )
    (net (code "78") (name "unconnected-(J7-Pad2)") (class "Default")
      (node (ref "J7") (pin "2") (pinfunction "2_2") (pintype "passive"))
    )
    (net (code "79") (name "unconnected-(J7-Pad3)") (class "Default")
      (node (ref "J7") (pin "3") (pinfunction "3_3") (pintype "passive"))
    )
    (net (code "80") (name "unconnected-(J7-Pad4)") (class "Default")
      (node (ref "J7") (pin "4") (pinfunction "4_4") (pintype "passive"))
    )
    (net (code "81") (name "unconnected-(J7-Pad5)") (class "Default")
      (node (ref "J7") (pin "5") (pinfunction "5_5") (pintype "passive"))
    )
    (net (code "82") (name "unconnected-(J7-Pad6)") (class "Default")
      (node (ref "J7") (pin "6") (pinfunction "6_6") (pintype "passive"))
    )
    (net (code "83") (name "unconnected-(J7-Pad7)") (class "Default")
      (node (ref "J7") (pin "7") (pinfunction "7_7") (pintype "passive"))
    )
    (net (code "84") (name "unconnected-(J7-Pad8)") (class "Default")
      (node (ref "J7") (pin "8") (pinfunction "8_8") (pintype "passive"))
    )
    (net (code "85") (name "unconnected-(J7-Pad9)") (class "Default")
      (node (ref "J7") (pin "9") (pinfunction "9_9") (pintype "passive"))
    )
    (net (code "86") (name "unconnected-(J7-Pad10)") (class "Default")
      (node (ref "J7") (pin "10") (pinfunction "10_10") (pintype "passive"))
    )
    (net (code "87") (name "unconnected-(J8-Pad1)") (class "Default")
      (node (ref "J8") (pin "1") (pinfunction "1_1") (pintype "passive"))
    )
    (net (code "88") (name "unconnected-(J8-Pad2)") (class "Default")
      (node (ref "J8") (pin "2") (pinfunction "2_2") (pintype "passive"))
    )
    (net (code "89") (name "unconnected-(J8-Pad3)") (class "Default")
      (node (ref "J8") (pin "3") (pinfunction "3_3") (pintype "passive"))
    )
    (net (code "90") (name "unconnected-(J8-Pad4)") (class "Default")
      (node (ref "J8") (pin "4") (pinfunction "4_4") (pintype "passive"))
    )
    (net (code "91") (name "unconnected-(J8-Pad5)") (class "Default")
      (node (ref "J8") (pin "5") (pinfunction "5_5") (pintype "passive"))
    )
    (net (code "92") (name "unconnected-(J8-Pad6)") (class "Default")
      (node (ref "J8") (pin "6") (pinfunction "6_6") (pintype "passive"))
    )
    (net (code "93") (name "unconnected-(J8-Pad7)") (class "Default")
      (node (ref "J8") (pin "7") (pinfunction "7_7") (pintype "passive"))
    )
    (net (code "94") (name "unconnected-(J8-Pad8)") (class "Default")
      (node (ref "J8") (pin "8") (pinfunction "8_8") (pintype "passive"))
    )
    (net (code "95") (name "unconnected-(J8-Pad9)") (class "Default")
      (node (ref "J8") (pin "9") (pinfunction "9_9") (pintype "passive"))
    )
    (net (code "96") (name "unconnected-(J8-Pad10)") (class "Default")
      (node (ref "J8") (pin "10") (pinfunction "10_10") (pintype "passive"))
    )
    (net (code "97") (name "unconnected-(S6-Pad1)") (class "Default")
      (node (ref "S6") (pin "1") (pinfunction "1_1") (pintype "passive"))
    )
  )
)
